# BarrKeeb16.net
KiCad netlist of a schematic drawn in EAGLE
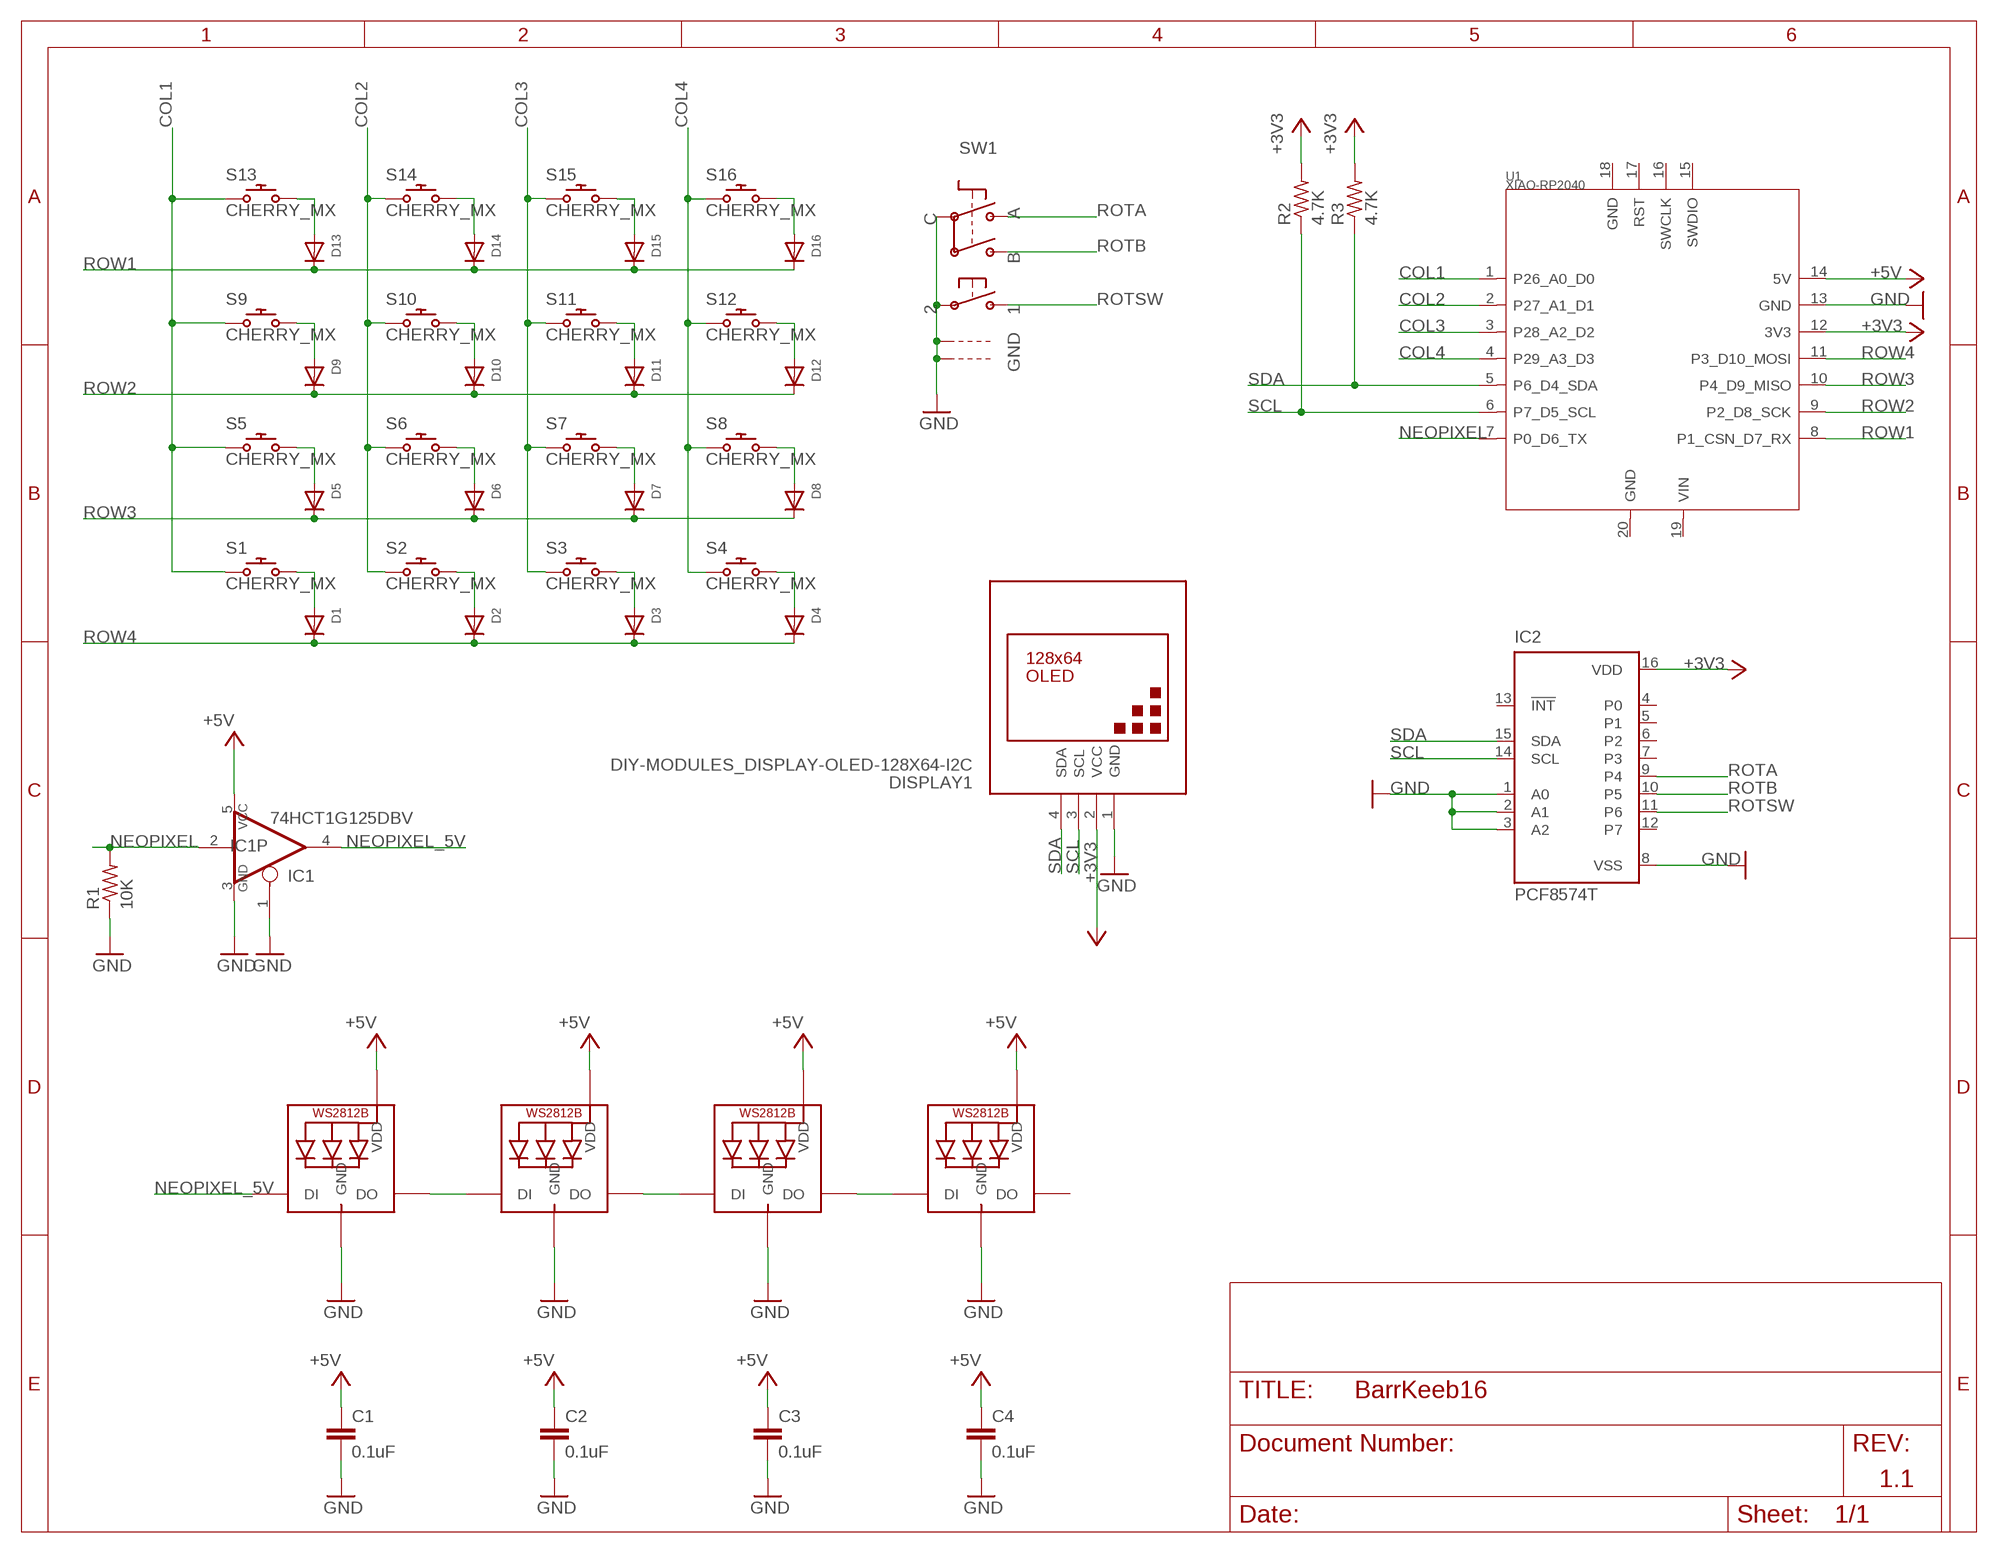
[diagram p0: schematic, sheet 1]

(export (version "E")
  (design (tool "Eeschema 10.0.6"))
  (components
    (comp (ref "C1")
      (value "0.1uF")
      (footprint "eagle-import:0603")
      (libsource (lib "eagle-import") (part "0.1UF-0603-25V-(+80/-20%)"))
    )
    (comp (ref "C2")
      (value "0.1uF")
      (footprint "eagle-import:0603")
      (libsource (lib "eagle-import") (part "0.1UF-0603-25V-(+80/-20%)"))
    )
    (comp (ref "C3")
      (value "0.1uF")
      (footprint "eagle-import:0603")
      (libsource (lib "eagle-import") (part "0.1UF-0603-25V-(+80/-20%)"))
    )
    (comp (ref "C4")
      (value "0.1uF")
      (footprint "eagle-import:0603")
      (libsource (lib "eagle-import") (part "0.1UF-0603-25V-(+80/-20%)"))
    )
    (comp (ref "D1")
      (value "MICROBUILDER_DIODESOD-123")
      (footprint "eagle-import:MICROBUILDER_SOD-123")
      (libsource (lib "eagle-import") (part "MICROBUILDER_DIODESOD-123"))
    )
    (comp (ref "D2")
      (value "MICROBUILDER_DIODESOD-123")
      (footprint "eagle-import:MICROBUILDER_SOD-123")
      (libsource (lib "eagle-import") (part "MICROBUILDER_DIODESOD-123"))
    )
    (comp (ref "D3")
      (value "MICROBUILDER_DIODESOD-123")
      (footprint "eagle-import:MICROBUILDER_SOD-123")
      (libsource (lib "eagle-import") (part "MICROBUILDER_DIODESOD-123"))
    )
    (comp (ref "D4")
      (value "MICROBUILDER_DIODESOD-123")
      (footprint "eagle-import:MICROBUILDER_SOD-123")
      (libsource (lib "eagle-import") (part "MICROBUILDER_DIODESOD-123"))
    )
    (comp (ref "D5")
      (value "MICROBUILDER_DIODESOD-123")
      (footprint "eagle-import:MICROBUILDER_SOD-123")
      (libsource (lib "eagle-import") (part "MICROBUILDER_DIODESOD-123"))
    )
    (comp (ref "D6")
      (value "MICROBUILDER_DIODESOD-123")
      (footprint "eagle-import:MICROBUILDER_SOD-123")
      (libsource (lib "eagle-import") (part "MICROBUILDER_DIODESOD-123"))
    )
    (comp (ref "D7")
      (value "MICROBUILDER_DIODESOD-123")
      (footprint "eagle-import:MICROBUILDER_SOD-123")
      (libsource (lib "eagle-import") (part "MICROBUILDER_DIODESOD-123"))
    )
    (comp (ref "D8")
      (value "MICROBUILDER_DIODESOD-123")
      (footprint "eagle-import:MICROBUILDER_SOD-123")
      (libsource (lib "eagle-import") (part "MICROBUILDER_DIODESOD-123"))
    )
    (comp (ref "D9")
      (value "MICROBUILDER_DIODESOD-123")
      (footprint "eagle-import:MICROBUILDER_SOD-123")
      (libsource (lib "eagle-import") (part "MICROBUILDER_DIODESOD-123"))
    )
    (comp (ref "D10")
      (value "MICROBUILDER_DIODESOD-123")
      (footprint "eagle-import:MICROBUILDER_SOD-123")
      (libsource (lib "eagle-import") (part "MICROBUILDER_DIODESOD-123"))
    )
    (comp (ref "D11")
      (value "MICROBUILDER_DIODESOD-123")
      (footprint "eagle-import:MICROBUILDER_SOD-123")
      (libsource (lib "eagle-import") (part "MICROBUILDER_DIODESOD-123"))
    )
    (comp (ref "D12")
      (value "MICROBUILDER_DIODESOD-123")
      (footprint "eagle-import:MICROBUILDER_SOD-123")
      (libsource (lib "eagle-import") (part "MICROBUILDER_DIODESOD-123"))
    )
    (comp (ref "D13")
      (value "MICROBUILDER_DIODESOD-123")
      (footprint "eagle-import:MICROBUILDER_SOD-123")
      (libsource (lib "eagle-import") (part "MICROBUILDER_DIODESOD-123"))
    )
    (comp (ref "D14")
      (value "MICROBUILDER_DIODESOD-123")
      (footprint "eagle-import:MICROBUILDER_SOD-123")
      (libsource (lib "eagle-import") (part "MICROBUILDER_DIODESOD-123"))
    )
    (comp (ref "D15")
      (value "MICROBUILDER_DIODESOD-123")
      (footprint "eagle-import:MICROBUILDER_SOD-123")
      (libsource (lib "eagle-import") (part "MICROBUILDER_DIODESOD-123"))
    )
    (comp (ref "D16")
      (value "MICROBUILDER_DIODESOD-123")
      (footprint "eagle-import:MICROBUILDER_SOD-123")
      (libsource (lib "eagle-import") (part "MICROBUILDER_DIODESOD-123"))
    )
    (comp (ref "DISPLAY1")
      (value "DIY-MODULES_DISPLAY-OLED-128X64-I2C")
      (footprint "eagle-import:DIY-MODULES_DISPLAY-OLED-128X64-I2C")
      (libsource (lib "eagle-import") (part "DIY-MODULES_DISPLAY-OLED-128X64-I2C"))
    )
    (comp (ref "IC1")
      (value "74HCT1G125DBV")
      (footprint "eagle-import:SOT23-5")
      (libsource (lib "eagle-import") (part "741G125DBVAHC"))
    )
    (comp (ref "IC2")
      (value "PCF8574T")
      (footprint "eagle-import:SO16W")
      (fields (field (name "MPN") "PCF8574T/3,512"))
      (libsource (lib "eagle-import") (part "PCF8574T"))
    )
    (comp (ref "LED1")
      (value "WS2812B5050")
      (footprint "eagle-import:WS2812B")
      (libsource (lib "eagle-import") (part "WS2812B5050"))
    )
    (comp (ref "LED2")
      (value "WS2812B5050")
      (footprint "eagle-import:WS2812B")
      (libsource (lib "eagle-import") (part "WS2812B5050"))
    )
    (comp (ref "LED3")
      (value "WS2812B5050")
      (footprint "eagle-import:WS2812B")
      (libsource (lib "eagle-import") (part "WS2812B5050"))
    )
    (comp (ref "LED4")
      (value "WS2812B5050")
      (footprint "eagle-import:WS2812B")
      (libsource (lib "eagle-import") (part "WS2812B5050"))
    )
    (comp (ref "R1")
      (value "10K")
      (footprint "eagle-import:R0805")
      (libsource (lib "eagle-import") (part "R-US_R0805"))
    )
    (comp (ref "R2")
      (value "4.7K")
      (footprint "eagle-import:R0805")
      (libsource (lib "eagle-import") (part "R-US_R0805"))
    )
    (comp (ref "R3")
      (value "4.7K")
      (footprint "eagle-import:R0805")
      (libsource (lib "eagle-import") (part "R-US_R0805"))
    )
    (comp (ref "S1")
      (value "CHERRY_MX")
      (footprint "eagle-import:CHERRY_MX")
      (libsource (lib "eagle-import") (part "CHERRY_MX"))
    )
    (comp (ref "S2")
      (value "CHERRY_MX")
      (footprint "eagle-import:CHERRY_MX")
      (libsource (lib "eagle-import") (part "CHERRY_MX"))
    )
    (comp (ref "S3")
      (value "CHERRY_MX")
      (footprint "eagle-import:CHERRY_MX")
      (libsource (lib "eagle-import") (part "CHERRY_MX"))
    )
    (comp (ref "S4")
      (value "CHERRY_MX")
      (footprint "eagle-import:CHERRY_MX")
      (libsource (lib "eagle-import") (part "CHERRY_MX"))
    )
    (comp (ref "S5")
      (value "CHERRY_MX")
      (footprint "eagle-import:CHERRY_MX")
      (libsource (lib "eagle-import") (part "CHERRY_MX"))
    )
    (comp (ref "S6")
      (value "CHERRY_MX")
      (footprint "eagle-import:CHERRY_MX")
      (libsource (lib "eagle-import") (part "CHERRY_MX"))
    )
    (comp (ref "S7")
      (value "CHERRY_MX")
      (footprint "eagle-import:CHERRY_MX")
      (libsource (lib "eagle-import") (part "CHERRY_MX"))
    )
    (comp (ref "S8")
      (value "CHERRY_MX")
      (footprint "eagle-import:CHERRY_MX")
      (libsource (lib "eagle-import") (part "CHERRY_MX"))
    )
    (comp (ref "S9")
      (value "CHERRY_MX")
      (footprint "eagle-import:CHERRY_MX")
      (libsource (lib "eagle-import") (part "CHERRY_MX"))
    )
    (comp (ref "S10")
      (value "CHERRY_MX")
      (footprint "eagle-import:CHERRY_MX")
      (libsource (lib "eagle-import") (part "CHERRY_MX"))
    )
    (comp (ref "S11")
      (value "CHERRY_MX")
      (footprint "eagle-import:CHERRY_MX")
      (libsource (lib "eagle-import") (part "CHERRY_MX"))
    )
    (comp (ref "S12")
      (value "CHERRY_MX")
      (footprint "eagle-import:CHERRY_MX")
      (libsource (lib "eagle-import") (part "CHERRY_MX"))
    )
    (comp (ref "S13")
      (value "CHERRY_MX")
      (footprint "eagle-import:CHERRY_MX")
      (libsource (lib "eagle-import") (part "CHERRY_MX"))
    )
    (comp (ref "S14")
      (value "CHERRY_MX")
      (footprint "eagle-import:CHERRY_MX")
      (libsource (lib "eagle-import") (part "CHERRY_MX"))
    )
    (comp (ref "S15")
      (value "CHERRY_MX")
      (footprint "eagle-import:CHERRY_MX")
      (libsource (lib "eagle-import") (part "CHERRY_MX"))
    )
    (comp (ref "S16")
      (value "CHERRY_MX")
      (footprint "eagle-import:CHERRY_MX")
      (libsource (lib "eagle-import") (part "CHERRY_MX"))
    )
    (comp (ref "SW1")
      (value "ADAFRUIT_ELECTROMECH_ENCODER_PLUS_SWITCH_BOURNS_PEC11")
      (footprint "eagle-import:ADAFRUIT_ELECTROMECH_PEC11+SWITCH")
      (libsource (lib "eagle-import") (part "ADAFRUIT_ELECTROMECH_ENCODER_PLUS_SWITCH_PEC11_BOURNS"))
    )
    (comp (ref "U1")
      (value "XIAO-RP2040")
      (footprint "eagle-import:XIAO-SAMD21_RP2040-MODULE14P-2.54-21X17.8MM")
      (libsource (lib "eagle-import") (part "XIAO-RP2040"))
    )
  )
  (nets
    (net (code "1") (name "+3V3") (class "Default")
      (node (ref "DISPLAY1") (pin "2") (pinfunction "VCC_2") (pintype "bidirectional"))
      (node (ref "IC2") (pin "16") (pinfunction "VDD_16") (pintype "power_in"))
      (node (ref "R2") (pin "2") (pinfunction "2_2") (pintype "passive"))
      (node (ref "R3") (pin "2") (pinfunction "2_2") (pintype "passive"))
      (node (ref "U1") (pin "12") (pinfunction "3V3_12") (pintype "bidirectional"))
    )
    (net (code "2") (name "+5V") (class "Default")
      (node (ref "C1") (pin "1") (pinfunction "1_1") (pintype "passive"))
      (node (ref "C2") (pin "1") (pinfunction "1_1") (pintype "passive"))
      (node (ref "C3") (pin "1") (pinfunction "1_1") (pintype "passive"))
      (node (ref "C4") (pin "1") (pinfunction "1_1") (pintype "passive"))
      (node (ref "IC1") (pin "5") (pinfunction "VCC_5") (pintype "power_in"))
      (node (ref "LED1") (pin "1-VDD") (pinfunction "VDD_1-VDD") (pintype "power_in"))
      (node (ref "LED2") (pin "1-VDD") (pinfunction "VDD_1-VDD") (pintype "power_in"))
      (node (ref "LED3") (pin "1-VDD") (pinfunction "VDD_1-VDD") (pintype "power_in"))
      (node (ref "LED4") (pin "1-VDD") (pinfunction "VDD_1-VDD") (pintype "power_in"))
      (node (ref "U1") (pin "14") (pinfunction "5V_14") (pintype "bidirectional"))
    )
    (net (code "3") (name "/COL1") (class "Default")
      (node (ref "S1") (pin "S1") (pinfunction "1_S1") (pintype "passive"))
      (node (ref "S13") (pin "S1") (pinfunction "1_S1") (pintype "passive"))
      (node (ref "S5") (pin "S1") (pinfunction "1_S1") (pintype "passive"))
      (node (ref "S9") (pin "S1") (pinfunction "1_S1") (pintype "passive"))
      (node (ref "U1") (pin "1") (pinfunction "P26_A0_D0_1") (pintype "bidirectional"))
    )
    (net (code "4") (name "/COL2") (class "Default")
      (node (ref "S10") (pin "S1") (pinfunction "1_S1") (pintype "passive"))
      (node (ref "S14") (pin "S1") (pinfunction "1_S1") (pintype "passive"))
      (node (ref "S2") (pin "S1") (pinfunction "1_S1") (pintype "passive"))
      (node (ref "S6") (pin "S1") (pinfunction "1_S1") (pintype "passive"))
      (node (ref "U1") (pin "2") (pinfunction "P27_A1_D1_2") (pintype "bidirectional"))
    )
    (net (code "5") (name "/COL3") (class "Default")
      (node (ref "S11") (pin "S1") (pinfunction "1_S1") (pintype "passive"))
      (node (ref "S15") (pin "S1") (pinfunction "1_S1") (pintype "passive"))
      (node (ref "S3") (pin "S1") (pinfunction "1_S1") (pintype "passive"))
      (node (ref "S7") (pin "S1") (pinfunction "1_S1") (pintype "passive"))
      (node (ref "U1") (pin "3") (pinfunction "P28_A2_D2_3") (pintype "bidirectional"))
    )
    (net (code "6") (name "/COL4") (class "Default")
      (node (ref "S12") (pin "S1") (pinfunction "1_S1") (pintype "passive"))
      (node (ref "S16") (pin "S1") (pinfunction "1_S1") (pintype "passive"))
      (node (ref "S4") (pin "S1") (pinfunction "1_S1") (pintype "passive"))
      (node (ref "S8") (pin "S1") (pinfunction "1_S1") (pintype "passive"))
      (node (ref "U1") (pin "4") (pinfunction "P29_A3_D3_4") (pintype "bidirectional"))
    )
    (net (code "7") (name "/NEOPIXEL") (class "Default")
      (node (ref "IC1") (pin "2") (pinfunction "I_2") (pintype "input"))
      (node (ref "R1") (pin "2") (pinfunction "2_2") (pintype "passive"))
      (node (ref "U1") (pin "7") (pinfunction "P0_D6_TX_7") (pintype "bidirectional"))
    )
    (net (code "8") (name "/NEOPIXEL_5V") (class "Default")
      (node (ref "IC1") (pin "4") (pinfunction "O_4") (pintype "tri_state"))
      (node (ref "LED1") (pin "4-DIN") (pinfunction "DI_4-DIN") (pintype "input"))
    )
    (net (code "9") (name "/ROTA") (class "Default")
      (node (ref "IC2") (pin "9") (pinfunction "P4_9") (pintype "bidirectional"))
      (node (ref "SW1") (pin "P$A") (pinfunction "P$A_P$A") (pintype "passive"))
    )
    (net (code "10") (name "/ROTB") (class "Default")
      (node (ref "IC2") (pin "10") (pinfunction "P5_10") (pintype "bidirectional"))
      (node (ref "SW1") (pin "P$B") (pinfunction "P$B_P$B") (pintype "passive"))
    )
    (net (code "11") (name "/ROTSW") (class "Default")
      (node (ref "IC2") (pin "11") (pinfunction "P6_11") (pintype "bidirectional"))
      (node (ref "SW1") (pin "P$1") (pinfunction "P$1_P$1") (pintype "passive"))
    )
    (net (code "12") (name "/ROW1") (class "Default")
      (node (ref "D13") (pin "C") (pinfunction "C_C") (pintype "passive"))
      (node (ref "D14") (pin "C") (pinfunction "C_C") (pintype "passive"))
      (node (ref "D15") (pin "C") (pinfunction "C_C") (pintype "passive"))
      (node (ref "D16") (pin "C") (pinfunction "C_C") (pintype "passive"))
      (node (ref "U1") (pin "8") (pinfunction "P1_CSN_D7_RX_8") (pintype "bidirectional"))
    )
    (net (code "13") (name "/ROW2") (class "Default")
      (node (ref "D10") (pin "C") (pinfunction "C_C") (pintype "passive"))
      (node (ref "D11") (pin "C") (pinfunction "C_C") (pintype "passive"))
      (node (ref "D12") (pin "C") (pinfunction "C_C") (pintype "passive"))
      (node (ref "D9") (pin "C") (pinfunction "C_C") (pintype "passive"))
      (node (ref "U1") (pin "9") (pinfunction "P2_D8_SCK_9") (pintype "bidirectional"))
    )
    (net (code "14") (name "/ROW3") (class "Default")
      (node (ref "D5") (pin "C") (pinfunction "C_C") (pintype "passive"))
      (node (ref "D6") (pin "C") (pinfunction "C_C") (pintype "passive"))
      (node (ref "D7") (pin "C") (pinfunction "C_C") (pintype "passive"))
      (node (ref "D8") (pin "C") (pinfunction "C_C") (pintype "passive"))
      (node (ref "U1") (pin "10") (pinfunction "P4_D9_MISO_10") (pintype "bidirectional"))
    )
    (net (code "15") (name "/ROW4") (class "Default")
      (node (ref "D1") (pin "C") (pinfunction "C_C") (pintype "passive"))
      (node (ref "D2") (pin "C") (pinfunction "C_C") (pintype "passive"))
      (node (ref "D3") (pin "C") (pinfunction "C_C") (pintype "passive"))
      (node (ref "D4") (pin "C") (pinfunction "C_C") (pintype "passive"))
      (node (ref "U1") (pin "11") (pinfunction "P3_D10_MOSI_11") (pintype "bidirectional"))
    )
    (net (code "16") (name "/SCL") (class "Default")
      (node (ref "DISPLAY1") (pin "3") (pinfunction "SCL_3") (pintype "bidirectional"))
      (node (ref "IC2") (pin "14") (pinfunction "SCL_14") (pintype "input"))
      (node (ref "R2") (pin "1") (pinfunction "1_1") (pintype "passive"))
      (node (ref "U1") (pin "6") (pinfunction "P7_D5_SCL_6") (pintype "bidirectional"))
    )
    (net (code "17") (name "/SDA") (class "Default")
      (node (ref "DISPLAY1") (pin "4") (pinfunction "SDA_4") (pintype "bidirectional"))
      (node (ref "IC2") (pin "15") (pinfunction "SDA_15") (pintype "bidirectional"))
      (node (ref "R3") (pin "1") (pinfunction "1_1") (pintype "passive"))
      (node (ref "U1") (pin "5") (pinfunction "P6_D4_SDA_5") (pintype "bidirectional"))
    )
    (net (code "18") (name "GND") (class "Default")
      (node (ref "C1") (pin "2") (pinfunction "2_2") (pintype "passive"))
      (node (ref "C2") (pin "2") (pinfunction "2_2") (pintype "passive"))
      (node (ref "C3") (pin "2") (pinfunction "2_2") (pintype "passive"))
      (node (ref "C4") (pin "2") (pinfunction "2_2") (pintype "passive"))
      (node (ref "DISPLAY1") (pin "1") (pinfunction "GND_1") (pintype "bidirectional"))
      (node (ref "IC1") (pin "1") (pinfunction "OE_1") (pintype "input"))
      (node (ref "IC1") (pin "3") (pinfunction "GND_3") (pintype "power_in"))
      (node (ref "IC2") (pin "1") (pinfunction "A0_1") (pintype "input"))
      (node (ref "IC2") (pin "2") (pinfunction "A1_2") (pintype "input"))
      (node (ref "IC2") (pin "3") (pinfunction "A2_3") (pintype "input"))
      (node (ref "IC2") (pin "8") (pinfunction "VSS_8") (pintype "power_in"))
      (node (ref "LED1") (pin "3-GND") (pinfunction "GND_3-GND") (pintype "power_in"))
      (node (ref "LED2") (pin "3-GND") (pinfunction "GND_3-GND") (pintype "power_in"))
      (node (ref "LED3") (pin "3-GND") (pinfunction "GND_3-GND") (pintype "power_in"))
      (node (ref "LED4") (pin "3-GND") (pinfunction "GND_3-GND") (pintype "power_in"))
      (node (ref "R1") (pin "1") (pinfunction "1_1") (pintype "passive"))
      (node (ref "SW1") (pin "P$2") (pinfunction "P$2_P$2") (pintype "passive"))
      (node (ref "SW1") (pin "P$C") (pinfunction "P$C_P$C") (pintype "passive"))
      (node (ref "SW1") (pin "P$GND1") (pinfunction "P$GND1_P$GND1") (pintype "passive"))
      (node (ref "SW1") (pin "P$GND2") (pinfunction "P$GND2_P$GND2") (pintype "passive"))
      (node (ref "U1") (pin "13") (pinfunction "GND_13") (pintype "bidirectional"))
    )
    (net (code "19") (name "Net-(LED1-DO)") (class "Default")
      (node (ref "LED1") (pin "2-DOUT") (pinfunction "DO_2-DOUT") (pintype "output"))
      (node (ref "LED2") (pin "4-DIN") (pinfunction "DI_4-DIN") (pintype "input"))
    )
    (net (code "20") (name "Net-(LED2-DO)") (class "Default")
      (node (ref "LED2") (pin "2-DOUT") (pinfunction "DO_2-DOUT") (pintype "output"))
      (node (ref "LED3") (pin "4-DIN") (pinfunction "DI_4-DIN") (pintype "input"))
    )
    (net (code "21") (name "Net-(LED3-DO)") (class "Default")
      (node (ref "LED3") (pin "2-DOUT") (pinfunction "DO_2-DOUT") (pintype "output"))
      (node (ref "LED4") (pin "4-DIN") (pinfunction "DI_4-DIN") (pintype "input"))
    )
    (net (code "22") (name "Net-(S1-2)") (class "Default")
      (node (ref "D1") (pin "A") (pinfunction "A_A") (pintype "passive"))
      (node (ref "S1") (pin "S2") (pinfunction "2_S2") (pintype "passive"))
    )
    (net (code "23") (name "Net-(S2-2)") (class "Default")
      (node (ref "D2") (pin "A") (pinfunction "A_A") (pintype "passive"))
      (node (ref "S2") (pin "S2") (pinfunction "2_S2") (pintype "passive"))
    )
    (net (code "24") (name "Net-(S3-2)") (class "Default")
      (node (ref "D3") (pin "A") (pinfunction "A_A") (pintype "passive"))
      (node (ref "S3") (pin "S2") (pinfunction "2_S2") (pintype "passive"))
    )
    (net (code "25") (name "Net-(S4-2)") (class "Default")
      (node (ref "D4") (pin "A") (pinfunction "A_A") (pintype "passive"))
      (node (ref "S4") (pin "S2") (pinfunction "2_S2") (pintype "passive"))
    )
    (net (code "26") (name "Net-(S5-2)") (class "Default")
      (node (ref "D5") (pin "A") (pinfunction "A_A") (pintype "passive"))
      (node (ref "S5") (pin "S2") (pinfunction "2_S2") (pintype "passive"))
    )
    (net (code "27") (name "Net-(S6-2)") (class "Default")
      (node (ref "D6") (pin "A") (pinfunction "A_A") (pintype "passive"))
      (node (ref "S6") (pin "S2") (pinfunction "2_S2") (pintype "passive"))
    )
    (net (code "28") (name "Net-(S7-2)") (class "Default")
      (node (ref "D7") (pin "A") (pinfunction "A_A") (pintype "passive"))
      (node (ref "S7") (pin "S2") (pinfunction "2_S2") (pintype "passive"))
    )
    (net (code "29") (name "Net-(S8-2)") (class "Default")
      (node (ref "D8") (pin "A") (pinfunction "A_A") (pintype "passive"))
      (node (ref "S8") (pin "S2") (pinfunction "2_S2") (pintype "passive"))
    )
    (net (code "30") (name "Net-(S9-2)") (class "Default")
      (node (ref "D9") (pin "A") (pinfunction "A_A") (pintype "passive"))
      (node (ref "S9") (pin "S2") (pinfunction "2_S2") (pintype "passive"))
    )
    (net (code "31") (name "Net-(S10-2)") (class "Default")
      (node (ref "D10") (pin "A") (pinfunction "A_A") (pintype "passive"))
      (node (ref "S10") (pin "S2") (pinfunction "2_S2") (pintype "passive"))
    )
    (net (code "32") (name "Net-(S11-2)") (class "Default")
      (node (ref "D11") (pin "A") (pinfunction "A_A") (pintype "passive"))
      (node (ref "S11") (pin "S2") (pinfunction "2_S2") (pintype "passive"))
    )
    (net (code "33") (name "Net-(S12-2)") (class "Default")
      (node (ref "D12") (pin "A") (pinfunction "A_A") (pintype "passive"))
      (node (ref "S12") (pin "S2") (pinfunction "2_S2") (pintype "passive"))
    )
    (net (code "34") (name "Net-(S13-2)") (class "Default")
      (node (ref "D13") (pin "A") (pinfunction "A_A") (pintype "passive"))
      (node (ref "S13") (pin "S2") (pinfunction "2_S2") (pintype "passive"))
    )
    (net (code "35") (name "Net-(S14-2)") (class "Default")
      (node (ref "D14") (pin "A") (pinfunction "A_A") (pintype "passive"))
      (node (ref "S14") (pin "S2") (pinfunction "2_S2") (pintype "passive"))
    )
    (net (code "36") (name "Net-(S15-2)") (class "Default")
      (node (ref "D15") (pin "A") (pinfunction "A_A") (pintype "passive"))
      (node (ref "S15") (pin "S2") (pinfunction "2_S2") (pintype "passive"))
    )
    (net (code "37") (name "Net-(S16-2)") (class "Default")
      (node (ref "D16") (pin "A") (pinfunction "A_A") (pintype "passive"))
      (node (ref "S16") (pin "S2") (pinfunction "2_S2") (pintype "passive"))
    )
    (net (code "38") (name "unconnected-(IC2-P0-Pad4)") (class "Default")
      (node (ref "IC2") (pin "4") (pinfunction "P0_4") (pintype "bidirectional"))
    )
    (net (code "39") (name "unconnected-(IC2-P1-Pad5)") (class "Default")
      (node (ref "IC2") (pin "5") (pinfunction "P1_5") (pintype "bidirectional"))
    )
    (net (code "40") (name "unconnected-(IC2-P2-Pad6)") (class "Default")
      (node (ref "IC2") (pin "6") (pinfunction "P2_6") (pintype "bidirectional"))
    )
    (net (code "41") (name "unconnected-(IC2-P3-Pad7)") (class "Default")
      (node (ref "IC2") (pin "7") (pinfunction "P3_7") (pintype "bidirectional"))
    )
    (net (code "42") (name "unconnected-(IC2-P7-Pad12)") (class "Default")
      (node (ref "IC2") (pin "12") (pinfunction "P7_12") (pintype "bidirectional"))
    )
    (net (code "43") (name "unconnected-(IC2-~{INT}-Pad13)") (class "Default")
      (node (ref "IC2") (pin "13") (pinfunction "~{INT}_13") (pintype "output"))
    )
    (net (code "44") (name "unconnected-(LED4-DO-Pad2-DOUT)") (class "Default")
      (node (ref "LED4") (pin "2-DOUT") (pinfunction "DO_2-DOUT") (pintype "output"))
    )
    (net (code "45") (name "unconnected-(U1-GND-Pad18)") (class "Default")
      (node (ref "U1") (pin "18") (pinfunction "GND_18") (pintype "bidirectional"))
    )
    (net (code "46") (name "unconnected-(U1-GND-Pad20)") (class "Default")
      (node (ref "U1") (pin "20") (pinfunction "GND_20") (pintype "bidirectional"))
    )
    (net (code "47") (name "unconnected-(U1-RST-Pad17)") (class "Default")
      (node (ref "U1") (pin "17") (pinfunction "RST_17") (pintype "bidirectional"))
    )
    (net (code "48") (name "unconnected-(U1-SWCLK-Pad16)") (class "Default")
      (node (ref "U1") (pin "16") (pinfunction "SWCLK_16") (pintype "bidirectional"))
    )
    (net (code "49") (name "unconnected-(U1-SWDIO-Pad15)") (class "Default")
      (node (ref "U1") (pin "15") (pinfunction "SWDIO_15") (pintype "bidirectional"))
    )
    (net (code "50") (name "unconnected-(U1-VIN-Pad19)") (class "Default")
      (node (ref "U1") (pin "19") (pinfunction "VIN_19") (pintype "bidirectional"))
    )
  )
)
